# ENC28J60.net
KiCad netlist of a schematic drawn in Altium Designer
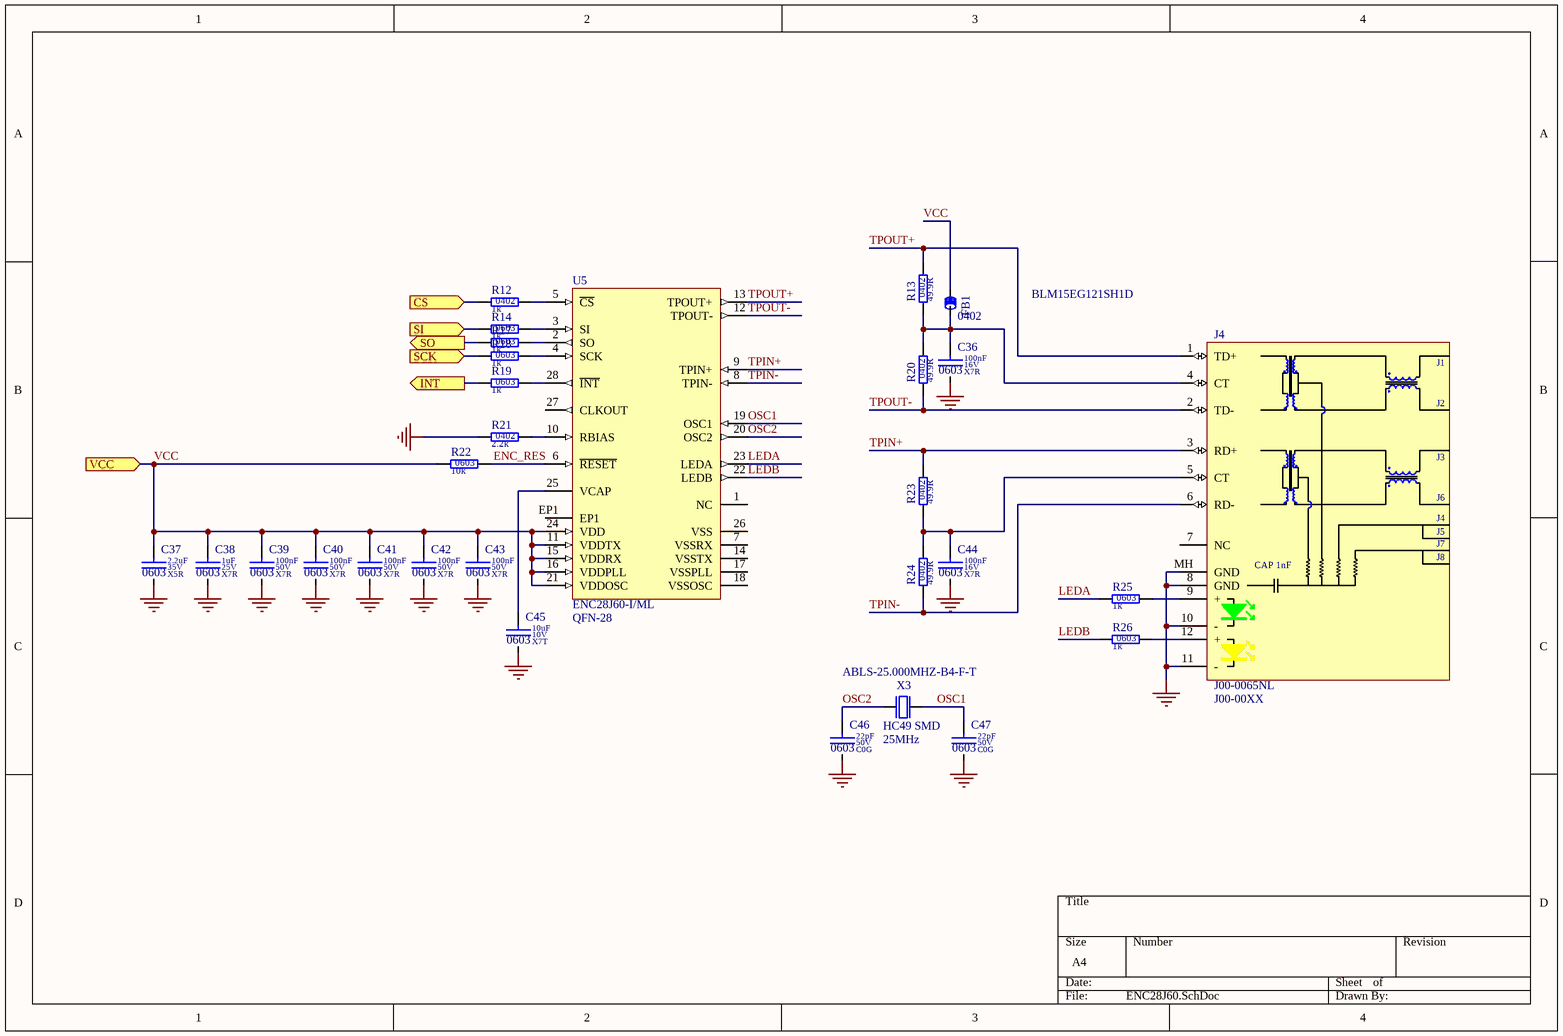
[diagram p0: ENC28J60.SchDoc]

(export (version "E")
  (design (tool "Eeschema 10.0.6"))
  (components
    (comp (ref "C36")
      (value "100nF")
      (footprint "C_0603_1608")
      (description "Capacitor")
      (fields
        (field (name "DIELECTRIC") "X7R")
        (field (name "VOLTAGE") "16V")
        (field (name "SCH_FOOTPRINT") "0603")
        (field (name "PART NUMBER") "C_100nF_16V_X7R_0603_10")
        (field (name "MANUFACTURER") "Kemet")
      )
      (libsource (lib "Library") (part "C"))
    )
    (comp (ref "C37")
      (value "2.2uF")
      (footprint "C_0603_1608")
      (description "Capacitor")
      (fields
        (field (name "DIELECTRIC") "X5R")
        (field (name "VOLTAGE") "35V")
        (field (name "SCH_FOOTPRINT") "0603")
        (field (name "PART NUMBER") "C_2.2uF_35V_X5R_0603_10")
        (field (name "MANUFACTURER") "Murata")
      )
      (libsource (lib "Library") (part "C"))
    )
    (comp (ref "C38")
      (value "1uF")
      (footprint "C_0603_1608")
      (description "Capacitor")
      (fields
        (field (name "DIELECTRIC") "X7R")
        (field (name "VOLTAGE") "25V")
        (field (name "SCH_FOOTPRINT") "0603")
        (field (name "PART NUMBER") "C_1uF_25V_X7R_0603_10")
        (field (name "MANUFACTURER") "Samsung")
      )
      (libsource (lib "Library") (part "C"))
    )
    (comp (ref "C39")
      (value "100nF")
      (footprint "C_0603_1608")
      (description "Capacitor")
      (fields
        (field (name "DIELECTRIC") "X7R")
        (field (name "VOLTAGE") "50V")
        (field (name "SCH_FOOTPRINT") "0603")
        (field (name "PART NUMBER") "C_100nF_50V_X7R_0603_5")
        (field (name "MANUFACTURER") "Samsung")
      )
      (libsource (lib "Library") (part "C"))
    )
    (comp (ref "C40")
      (value "100nF")
      (footprint "C_0603_1608")
      (description "Capacitor")
      (fields
        (field (name "DIELECTRIC") "X7R")
        (field (name "VOLTAGE") "50V")
        (field (name "SCH_FOOTPRINT") "0603")
        (field (name "PART NUMBER") "C_100nF_50V_X7R_0603_5")
        (field (name "MANUFACTURER") "Samsung")
      )
      (libsource (lib "Library") (part "C"))
    )
    (comp (ref "C41")
      (value "100nF")
      (footprint "C_0603_1608")
      (description "Capacitor")
      (fields
        (field (name "DIELECTRIC") "X7R")
        (field (name "VOLTAGE") "50V")
        (field (name "SCH_FOOTPRINT") "0603")
        (field (name "PART NUMBER") "C_100nF_50V_X7R_0603_5")
        (field (name "MANUFACTURER") "Samsung")
      )
      (libsource (lib "Library") (part "C"))
    )
    (comp (ref "C42")
      (value "100nF")
      (footprint "C_0603_1608")
      (description "Capacitor")
      (fields
        (field (name "DIELECTRIC") "X7R")
        (field (name "VOLTAGE") "50V")
        (field (name "SCH_FOOTPRINT") "0603")
        (field (name "PART NUMBER") "C_100nF_50V_X7R_0603_5")
        (field (name "MANUFACTURER") "Samsung")
      )
      (libsource (lib "Library") (part "C"))
    )
    (comp (ref "C43")
      (value "100nF")
      (footprint "C_0603_1608")
      (description "Capacitor")
      (fields
        (field (name "DIELECTRIC") "X7R")
        (field (name "VOLTAGE") "50V")
        (field (name "SCH_FOOTPRINT") "0603")
        (field (name "PART NUMBER") "C_100nF_50V_X7R_0603_5")
        (field (name "MANUFACTURER") "Samsung")
      )
      (libsource (lib "Library") (part "C"))
    )
    (comp (ref "C44")
      (value "100nF")
      (footprint "C_0603_1608")
      (description "Capacitor")
      (fields
        (field (name "DIELECTRIC") "X7R")
        (field (name "VOLTAGE") "16V")
        (field (name "SCH_FOOTPRINT") "0603")
        (field (name "PART NUMBER") "C_100nF_16V_X7R_0603_10")
        (field (name "MANUFACTURER") "Kemet")
      )
      (libsource (lib "Library") (part "C"))
    )
    (comp (ref "C45")
      (value "10uF")
      (footprint "C_0603_1608")
      (description "Capacitor")
      (fields
        (field (name "DIELECTRIC") "X7T")
        (field (name "VOLTAGE") "10V")
        (field (name "SCH_FOOTPRINT") "0603")
        (field (name "PART NUMBER") "C_10uF_10V_X7T_0603_20")
        (field (name "MANUFACTURER") "Murata")
      )
      (libsource (lib "Library") (part "C"))
    )
    (comp (ref "C46")
      (value "22pF")
      (footprint "C_0603_1608")
      (description "Capacitor")
      (fields
        (field (name "DIELECTRIC") "C0G")
        (field (name "VOLTAGE") "50V")
        (field (name "SCH_FOOTPRINT") "0603")
        (field (name "PART NUMBER") "C_22pF_50V_C0G_0603_5")
        (field (name "MANUFACTURER") "Yageo")
      )
      (libsource (lib "Library") (part "C"))
    )
    (comp (ref "C47")
      (value "22pF")
      (footprint "C_0603_1608")
      (description "Capacitor")
      (fields
        (field (name "DIELECTRIC") "C0G")
        (field (name "VOLTAGE") "50V")
        (field (name "SCH_FOOTPRINT") "0603")
        (field (name "PART NUMBER") "C_22pF_50V_C0G_0603_5")
        (field (name "MANUFACTURER") "Yageo")
      )
      (libsource (lib "Library") (part "C"))
    )
    (comp (ref "FB1")
      (value "BLM15EG121SH1D")
      (footprint "FB_0402_1005")
      (description "Ferrite Bead")
      (fields
        (field (name "PART NUMBER") "FB_BLM15EG121SH1D")
        (field (name "SCH_FOOTPRINT") "0402")
        (field (name "MANUFACTURER") "Murata")
      )
      (libsource (lib "Library") (part "FB"))
    )
    (comp (ref "J4")
      (value "J00-0065NL")
      (footprint "J00-00XX")
      (fields
        (field (name "SCH_FOOTPRINT") "J00-00XX")
        (field (name "PART NUMBER") "J_J00-0065NL")
        (field (name "MANUFACTURER") "Pulse")
        (field (name "Comment") "Modular Connectors / Ethernet Connectors 1X1 TAB DOWN 10/100")
      )
      (libsource (lib "Library") (part "J_J00-0065NL"))
    )
    (comp (ref "R12")
      (value "1k")
      (footprint "R_0402_1005")
      (fields
        (field (name "SCH_FOOTPRINT") "0402")
        (field (name "PART NUMBER") "R_1k_0402_1")
        (field (name "VOLTAGE") "50V")
        (field (name "POWER") "63mW")
      )
      (libsource (lib "Library") (part "R"))
    )
    (comp (ref "R13")
      (value "49.9R")
      (footprint "R_0402_1005")
      (fields
        (field (name "SCH_FOOTPRINT") "0402")
        (field (name "PART NUMBER") "R_49.9R_0402_1")
        (field (name "VOLTAGE") "50V")
        (field (name "POWER") "100mW")
      )
      (libsource (lib "Library") (part "R"))
    )
    (comp (ref "R14")
      (value "1k")
      (footprint "R_0603_1608")
      (fields
        (field (name "SCH_FOOTPRINT") "0603")
        (field (name "PART NUMBER") "R_1k_0603_1")
        (field (name "VOLTAGE") "75V")
        (field (name "POWER") "100mW")
      )
      (libsource (lib "Library") (part "R"))
    )
    (comp (ref "R17")
      (value "1k")
      (footprint "R_0603_1608")
      (fields
        (field (name "SCH_FOOTPRINT") "0603")
        (field (name "PART NUMBER") "R_1k_0603_1")
        (field (name "VOLTAGE") "75V")
        (field (name "POWER") "100mW")
      )
      (libsource (lib "Library") (part "R"))
    )
    (comp (ref "R18")
      (value "1k")
      (footprint "R_0603_1608")
      (fields
        (field (name "SCH_FOOTPRINT") "0603")
        (field (name "PART NUMBER") "R_1k_0603_1")
        (field (name "VOLTAGE") "75V")
        (field (name "POWER") "100mW")
      )
      (libsource (lib "Library") (part "R"))
    )
    (comp (ref "R19")
      (value "1k")
      (footprint "R_0603_1608")
      (fields
        (field (name "SCH_FOOTPRINT") "0603")
        (field (name "PART NUMBER") "R_1k_0603_1")
        (field (name "VOLTAGE") "75V")
        (field (name "POWER") "100mW")
      )
      (libsource (lib "Library") (part "R"))
    )
    (comp (ref "R20")
      (value "49.9R")
      (footprint "R_0402_1005")
      (fields
        (field (name "SCH_FOOTPRINT") "0402")
        (field (name "PART NUMBER") "R_49.9R_0402_1")
        (field (name "VOLTAGE") "50V")
        (field (name "POWER") "100mW")
      )
      (libsource (lib "Library") (part "R"))
    )
    (comp (ref "R21")
      (value "2.2k")
      (footprint "R_0402_1005")
      (fields
        (field (name "SCH_FOOTPRINT") "0402")
        (field (name "PART NUMBER") "R_2.2k_0402_1")
        (field (name "VOLTAGE") "50V")
        (field (name "POWER") "100mW")
      )
      (libsource (lib "Library") (part "R"))
    )
    (comp (ref "R22")
      (value "10k")
      (footprint "R_0603_1608")
      (fields
        (field (name "SCH_FOOTPRINT") "0603")
        (field (name "PART NUMBER") "R_10k_0603_1")
        (field (name "VOLTAGE") "75V")
        (field (name "POWER") "100mW")
      )
      (libsource (lib "Library") (part "R"))
    )
    (comp (ref "R23")
      (value "49.9R")
      (footprint "R_0402_1005")
      (fields
        (field (name "SCH_FOOTPRINT") "0402")
        (field (name "PART NUMBER") "R_49.9R_0402_1")
        (field (name "VOLTAGE") "50V")
        (field (name "POWER") "100mW")
      )
      (libsource (lib "Library") (part "R"))
    )
    (comp (ref "R24")
      (value "49.9R")
      (footprint "R_0402_1005")
      (fields
        (field (name "SCH_FOOTPRINT") "0402")
        (field (name "PART NUMBER") "R_49.9R_0402_1")
        (field (name "VOLTAGE") "50V")
        (field (name "POWER") "100mW")
      )
      (libsource (lib "Library") (part "R"))
    )
    (comp (ref "R25")
      (value "1k")
      (footprint "R_0603_1608")
      (fields
        (field (name "SCH_FOOTPRINT") "0603")
        (field (name "PART NUMBER") "R_1k_0603_1")
        (field (name "VOLTAGE") "75V")
        (field (name "POWER") "100mW")
      )
      (libsource (lib "Library") (part "R"))
    )
    (comp (ref "R26")
      (value "1k")
      (footprint "R_0603_1608")
      (fields
        (field (name "SCH_FOOTPRINT") "0603")
        (field (name "PART NUMBER") "R_1k_0603_1")
        (field (name "VOLTAGE") "75V")
        (field (name "POWER") "100mW")
      )
      (libsource (lib "Library") (part "R"))
    )
    (comp (ref "U5")
      (value "ENC28J60-I/ML")
      (footprint "QFN28_6x6_EP")
      (description "Series 3.3 V Stand-Alone Ethernet Controller with SPI Interface")
      (fields
        (field (name "SCH_FOOTPRINT") "QFN-28")
        (field (name "PART NUMBER") "U_ENC28J60-I/ML")
        (field (name "MANUFACTURER") "Microchip")
      )
      (libsource (lib "Library") (part "U_ENC28J60"))
    )
    (comp (ref "X3")
      (value "25MHz")
      (footprint "X_HC49_SMD")
      (description "Resonator Ceramic")
      (fields
        (field (name "PART NUMBER") "ABLS-25.000MHZ-B4-F-T")
        (field (name "MANUFACTURER PART NUMBER") "ABLS-25.000MHZ-B4-F-T")
        (field (name "SCH_FOOTPRINT") "HC49 SMD")
        (field (name "MANUFACTURER") "Abracon")
      )
      (libsource (lib "Library") (part "X_GENERIC"))
    )
  )
  (nets
    (net (code "1") (name "/CS") (class "Default")
      (node (ref "R12") (pin "1") (pinfunction "1_1") (pintype "passive"))
    )
    (net (code "2") (name "/ENC_RES") (class "Default")
      (node (ref "R22") (pin "2") (pinfunction "2_2") (pintype "passive"))
      (node (ref "U5") (pin "6") (pinfunction "~{RESET}_6") (pintype "input"))
    )
    (net (code "3") (name "/INT") (class "Default")
      (node (ref "R19") (pin "1") (pinfunction "1_1") (pintype "passive"))
    )
    (net (code "4") (name "/LEDA") (class "Default")
      (node (ref "R25") (pin "1") (pinfunction "1_1") (pintype "passive"))
      (node (ref "U5") (pin "23") (pinfunction "LEDA_23") (pintype "output"))
    )
    (net (code "5") (name "/LEDB") (class "Default")
      (node (ref "R26") (pin "1") (pinfunction "1_1") (pintype "passive"))
      (node (ref "U5") (pin "22") (pinfunction "LEDB_22") (pintype "output"))
    )
    (net (code "6") (name "/OSC1") (class "Default")
      (node (ref "C47") (pin "1") (pinfunction "1_1") (pintype "passive"))
      (node (ref "U5") (pin "19") (pinfunction "OSC1_19") (pintype "input"))
      (node (ref "X3") (pin "2") (pintype "passive"))
    )
    (net (code "7") (name "/OSC2") (class "Default")
      (node (ref "C46") (pin "1") (pinfunction "1_1") (pintype "passive"))
      (node (ref "U5") (pin "20") (pinfunction "OSC2_20") (pintype "output"))
      (node (ref "X3") (pin "1") (pintype "passive"))
    )
    (net (code "8") (name "/SCK") (class "Default")
      (node (ref "R18") (pin "1") (pinfunction "1_1") (pintype "passive"))
    )
    (net (code "9") (name "/SI") (class "Default")
      (node (ref "R14") (pin "1") (pinfunction "1_1") (pintype "passive"))
    )
    (net (code "10") (name "/SO") (class "Default")
      (node (ref "R17") (pin "1") (pinfunction "1_1") (pintype "passive"))
    )
    (net (code "11") (name "/TPIN+") (class "Default")
      (node (ref "J4") (pin "3") (pinfunction "RD+_3") (pintype "bidirectional"))
      (node (ref "R23") (pin "2") (pinfunction "2_2") (pintype "passive"))
      (node (ref "U5") (pin "9") (pinfunction "TPIN+_9") (pintype "input"))
    )
    (net (code "12") (name "/TPIN-") (class "Default")
      (node (ref "J4") (pin "6") (pinfunction "RD-_6") (pintype "bidirectional"))
      (node (ref "R24") (pin "1") (pinfunction "1_1") (pintype "passive"))
      (node (ref "U5") (pin "8") (pinfunction "TPIN-_8") (pintype "input"))
    )
    (net (code "13") (name "/TPOUT+") (class "Default")
      (node (ref "J4") (pin "1") (pinfunction "TD+_1") (pintype "bidirectional"))
      (node (ref "R13") (pin "2") (pinfunction "2_2") (pintype "passive"))
      (node (ref "U5") (pin "13") (pinfunction "TPOUT+_13") (pintype "output"))
    )
    (net (code "14") (name "/TPOUT-") (class "Default")
      (node (ref "J4") (pin "2") (pinfunction "TD-_2") (pintype "bidirectional"))
      (node (ref "R20") (pin "1") (pinfunction "1_1") (pintype "passive"))
      (node (ref "U5") (pin "12") (pinfunction "TPOUT-_12") (pintype "output"))
    )
    (net (code "15") (name "/VCC") (class "Default")
      (node (ref "C37") (pin "1") (pinfunction "1_1") (pintype "passive"))
      (node (ref "C38") (pin "1") (pinfunction "1_1") (pintype "passive"))
      (node (ref "C39") (pin "1") (pinfunction "1_1") (pintype "passive"))
      (node (ref "C40") (pin "1") (pinfunction "1_1") (pintype "passive"))
      (node (ref "C41") (pin "1") (pinfunction "1_1") (pintype "passive"))
      (node (ref "C42") (pin "1") (pinfunction "1_1") (pintype "passive"))
      (node (ref "C43") (pin "1") (pinfunction "1_1") (pintype "passive"))
      (node (ref "FB1") (pin "1") (pintype "passive"))
      (node (ref "R22") (pin "1") (pinfunction "1_1") (pintype "passive"))
      (node (ref "U5") (pin "11") (pinfunction "VDDTX_11") (pintype "input"))
      (node (ref "U5") (pin "15") (pinfunction "VDDRX_15") (pintype "input"))
      (node (ref "U5") (pin "16") (pinfunction "VDDPLL_16") (pintype "input"))
      (node (ref "U5") (pin "21") (pinfunction "VDDOSC_21") (pintype "input"))
      (node (ref "U5") (pin "24") (pinfunction "VDD_24") (pintype "input"))
    )
    (net (code "16") (name "GND") (class "Default")
      (node (ref "C36") (pin "2") (pinfunction "2_2") (pintype "passive"))
      (node (ref "C37") (pin "2") (pinfunction "2_2") (pintype "passive"))
      (node (ref "C38") (pin "2") (pinfunction "2_2") (pintype "passive"))
      (node (ref "C39") (pin "2") (pinfunction "2_2") (pintype "passive"))
      (node (ref "C40") (pin "2") (pinfunction "2_2") (pintype "passive"))
      (node (ref "C41") (pin "2") (pinfunction "2_2") (pintype "passive"))
      (node (ref "C42") (pin "2") (pinfunction "2_2") (pintype "passive"))
      (node (ref "C43") (pin "2") (pinfunction "2_2") (pintype "passive"))
      (node (ref "C44") (pin "2") (pinfunction "2_2") (pintype "passive"))
      (node (ref "C45") (pin "2") (pinfunction "2_2") (pintype "passive"))
      (node (ref "C46") (pin "2") (pinfunction "2_2") (pintype "passive"))
      (node (ref "C47") (pin "2") (pinfunction "2_2") (pintype "passive"))
      (node (ref "J4") (pin "10") (pinfunction "-_10") (pintype "passive"))
      (node (ref "J4") (pin "11") (pinfunction "-_11") (pintype "passive"))
      (node (ref "J4") (pin "8") (pinfunction "GND_8") (pintype "power_in"))
      (node (ref "J4") (pin "MH") (pinfunction "GND_MH") (pintype "power_in"))
      (node (ref "R21") (pin "1") (pinfunction "1_1") (pintype "passive"))
    )
    (net (code "17") (name "Net-(C36-Pad1)") (class "Default")
      (node (ref "C36") (pin "1") (pinfunction "1_1") (pintype "passive"))
      (node (ref "FB1") (pin "2") (pintype "passive"))
      (node (ref "J4") (pin "4") (pinfunction "CT_4") (pintype "bidirectional"))
      (node (ref "R13") (pin "1") (pinfunction "1_1") (pintype "passive"))
      (node (ref "R20") (pin "2") (pinfunction "2_2") (pintype "passive"))
    )
    (net (code "18") (name "Net-(C44-Pad1)") (class "Default")
      (node (ref "C44") (pin "1") (pinfunction "1_1") (pintype "passive"))
      (node (ref "J4") (pin "5") (pinfunction "CT_5") (pintype "bidirectional"))
      (node (ref "R23") (pin "1") (pinfunction "1_1") (pintype "passive"))
      (node (ref "R24") (pin "2") (pinfunction "2_2") (pintype "passive"))
    )
    (net (code "19") (name "Net-(J4-+-Pad9)") (class "Default")
      (node (ref "J4") (pin "9") (pinfunction "+_9") (pintype "passive"))
      (node (ref "R25") (pin "2") (pinfunction "2_2") (pintype "passive"))
    )
    (net (code "20") (name "Net-(J4-+-Pad12)") (class "Default")
      (node (ref "J4") (pin "12") (pinfunction "+_12") (pintype "passive"))
      (node (ref "R26") (pin "2") (pinfunction "2_2") (pintype "passive"))
    )
    (net (code "21") (name "Net-(U5-RBIAS)") (class "Default")
      (node (ref "R21") (pin "2") (pinfunction "2_2") (pintype "passive"))
      (node (ref "U5") (pin "10") (pinfunction "RBIAS_10") (pintype "input"))
    )
    (net (code "22") (name "Net-(U5-SCK)") (class "Default")
      (node (ref "R18") (pin "2") (pinfunction "2_2") (pintype "passive"))
      (node (ref "U5") (pin "4") (pinfunction "SCK_4") (pintype "input"))
    )
    (net (code "23") (name "Net-(U5-SI)") (class "Default")
      (node (ref "R14") (pin "2") (pinfunction "2_2") (pintype "passive"))
      (node (ref "U5") (pin "3") (pinfunction "SI_3") (pintype "input"))
    )
    (net (code "24") (name "Net-(U5-SO)") (class "Default")
      (node (ref "R17") (pin "2") (pinfunction "2_2") (pintype "passive"))
      (node (ref "U5") (pin "2") (pinfunction "SO_2") (pintype "output"))
    )
    (net (code "25") (name "Net-(U5-VCAP)") (class "Default")
      (node (ref "C45") (pin "1") (pinfunction "1_1") (pintype "passive"))
      (node (ref "U5") (pin "25") (pinfunction "VCAP_25") (pintype "power_in"))
    )
    (net (code "26") (name "Net-(U5-~{CS})") (class "Default")
      (node (ref "R12") (pin "2") (pinfunction "2_2") (pintype "passive"))
      (node (ref "U5") (pin "5") (pinfunction "~{CS}_5") (pintype "input"))
    )
    (net (code "27") (name "Net-(U5-~{INT})") (class "Default")
      (node (ref "R19") (pin "2") (pinfunction "2_2") (pintype "passive"))
      (node (ref "U5") (pin "28") (pinfunction "~{INT}_28") (pintype "output"))
    )
    (net (code "28") (name "unconnected-(J4-NC-Pad7)") (class "Default")
      (node (ref "J4") (pin "7") (pinfunction "NC_7") (pintype "passive"))
    )
    (net (code "29") (name "unconnected-(U5-CLKOUT-Pad27)") (class "Default")
      (node (ref "U5") (pin "27") (pinfunction "CLKOUT_27") (pintype "output"))
    )
    (net (code "30") (name "unconnected-(U5-NC-Pad1)") (class "Default")
      (node (ref "U5") (pin "1") (pinfunction "NC_1") (pintype "passive"))
    )
    (net (code "31") (name "unconnected-(U5-PadEP1)") (class "Default")
      (node (ref "U5") (pin "EP1") (pinfunction "EP1_EP1") (pintype "passive"))
    )
    (net (code "32") (name "unconnected-(U5-VSS-Pad26)") (class "Default")
      (node (ref "U5") (pin "26") (pinfunction "VSS_26") (pintype "power_in"))
    )
    (net (code "33") (name "unconnected-(U5-VSSOSC-Pad18)") (class "Default")
      (node (ref "U5") (pin "18") (pinfunction "VSSOSC_18") (pintype "power_in"))
    )
    (net (code "34") (name "unconnected-(U5-VSSPLL-Pad17)") (class "Default")
      (node (ref "U5") (pin "17") (pinfunction "VSSPLL_17") (pintype "power_in"))
    )
    (net (code "35") (name "unconnected-(U5-VSSRX-Pad7)") (class "Default")
      (node (ref "U5") (pin "7") (pinfunction "VSSRX_7") (pintype "power_in"))
    )
    (net (code "36") (name "unconnected-(U5-VSSTX-Pad14)") (class "Default")
      (node (ref "U5") (pin "14") (pinfunction "VSSTX_14") (pintype "power_in"))
    )
  )
)
